# Adafruit_Proto_Tripler_PiCowbell.net
KiCad netlist of a schematic drawn in EAGLE
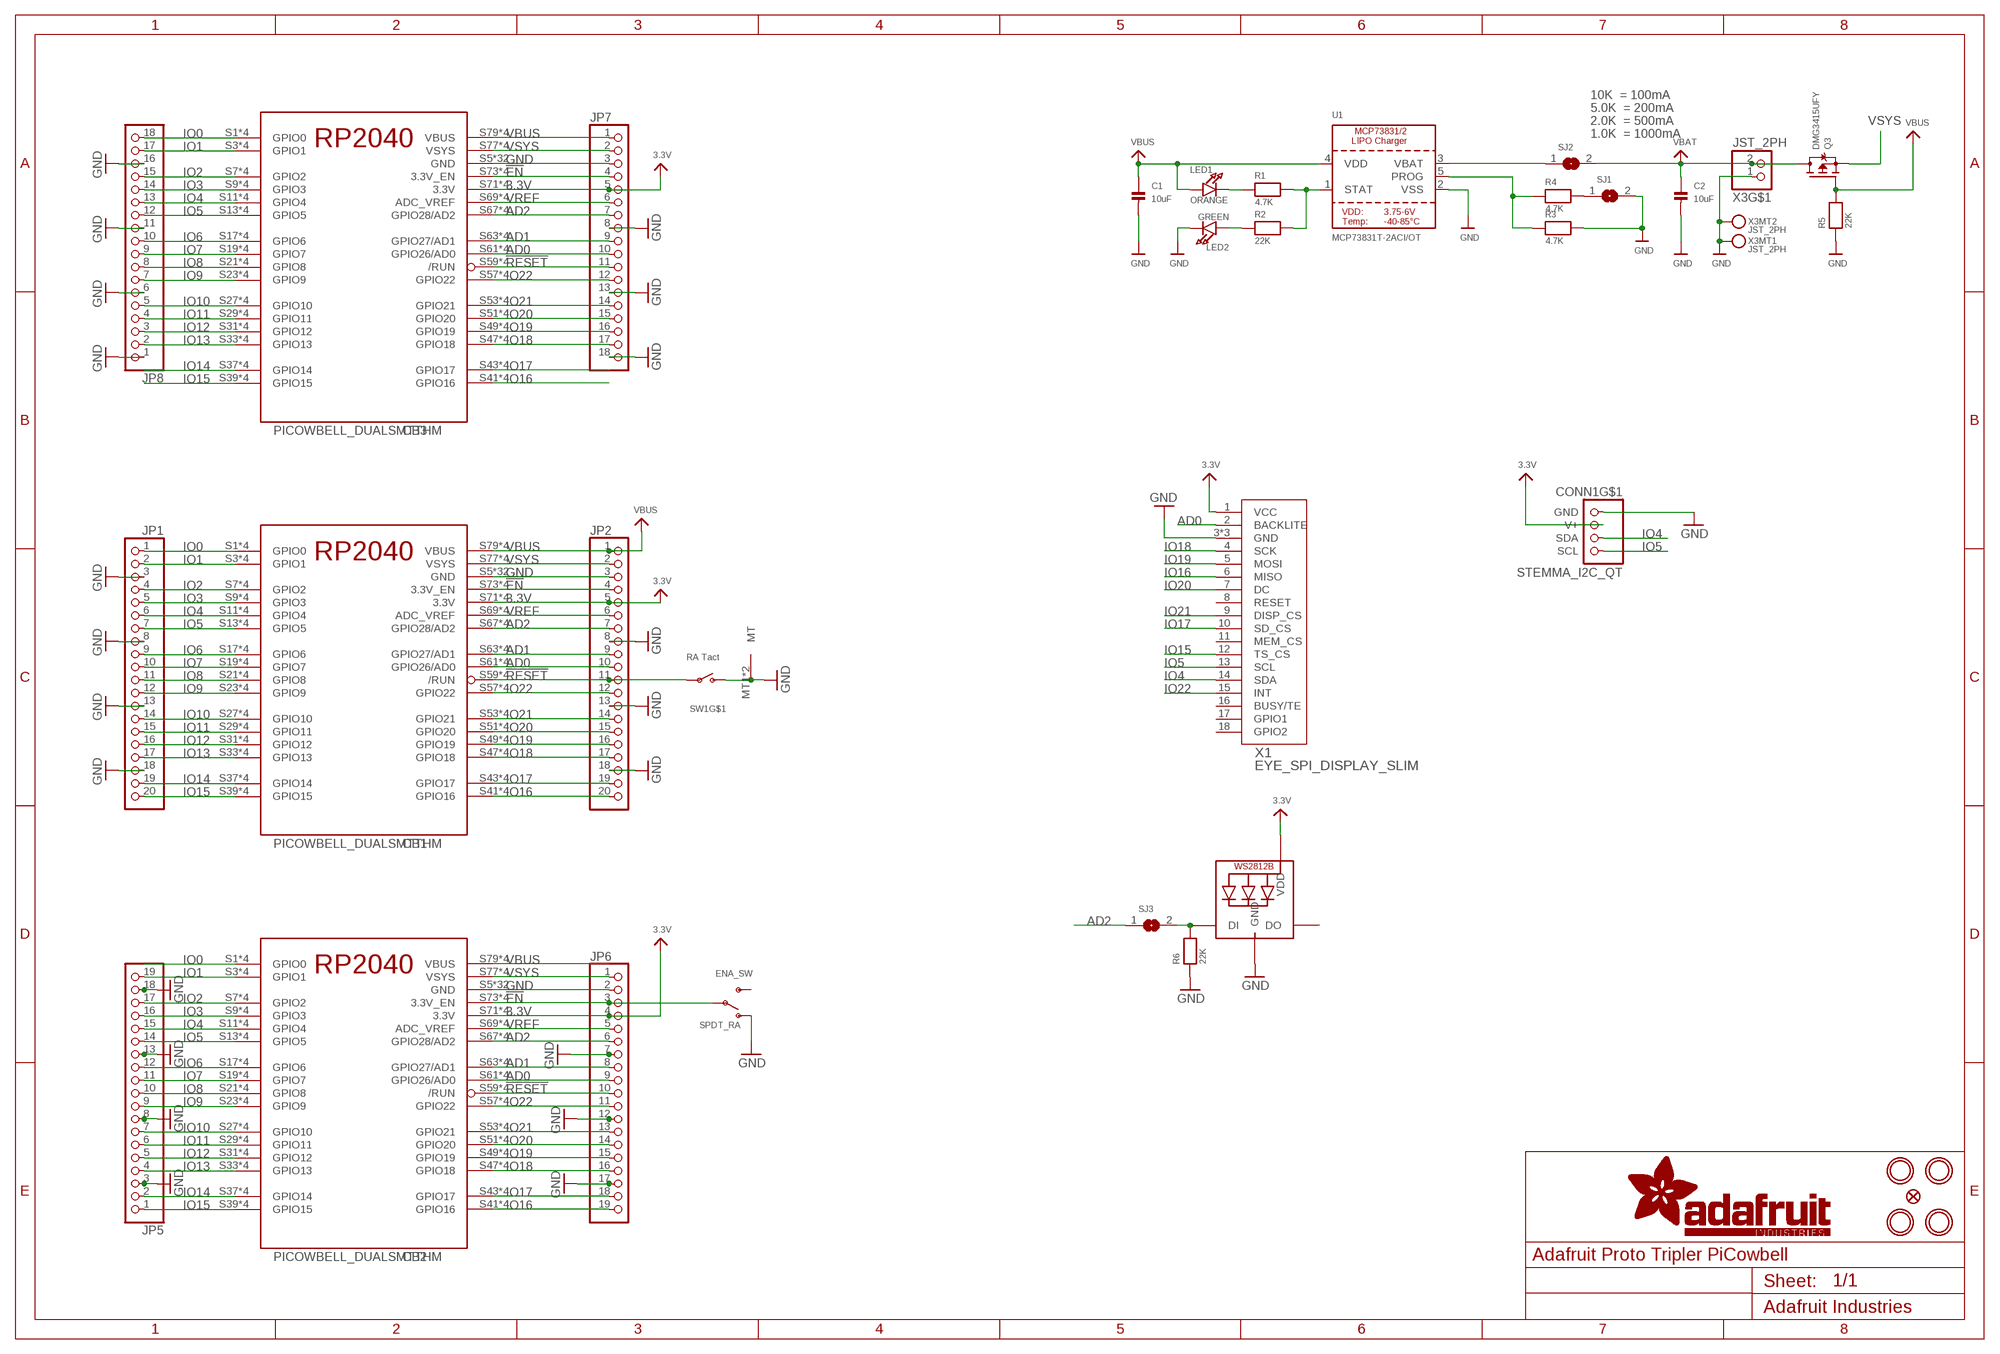
[diagram p0: schematic, sheet 1]

(export (version "E")
  (design (tool "Eeschema 10.0.6"))
  (components
    (comp (ref "C1")
      (value "10uF")
      (footprint "eagle-import:0805-NO")
      (libsource (lib "eagle-import") (part "CAP_CERAMIC0805-NOOUTLINE"))
    )
    (comp (ref "C2")
      (value "10uF")
      (footprint "eagle-import:0805-NO")
      (libsource (lib "eagle-import") (part "CAP_CERAMIC0805-NOOUTLINE"))
    )
    (comp (ref "CB1")
      (value "PICOWBELL_DUALSMTTHM")
      (footprint "eagle-import:PICOWBELL_DUALSMTTHM")
      (libsource (lib "eagle-import") (part "PICOWBELL_DUALSMTTHM"))
    )
    (comp (ref "CB2")
      (value "PICOWBELL_DUALSMTTHM")
      (footprint "eagle-import:PICOWBELL_DUALSMTTHM")
      (libsource (lib "eagle-import") (part "PICOWBELL_DUALSMTTHM"))
    )
    (comp (ref "CB3")
      (value "PICOWBELL_DUALSMTTHM")
      (footprint "eagle-import:PICOWBELL_DUALSMTTHM")
      (libsource (lib "eagle-import") (part "PICOWBELL_DUALSMTTHM"))
    )
    (comp (ref "CONN1")
      (value "STEMMA_I2C_QT")
      (footprint "eagle-import:JST_SH4")
      (libsource (lib "eagle-import") (part "STEMMA_I2C_QT"))
    )
    (comp (ref "ENA_SW")
      (value "SPDT_RA")
      (footprint "eagle-import:SPDT_SMT_SSSS811101")
      (libsource (lib "eagle-import") (part "SWITCH_SPDT"))
    )
    (comp (ref "FID2")
      (value "FIDUCIAL_1MM")
      (footprint "eagle-import:FIDUCIAL_1MM")
      (libsource (lib "eagle-import") (part "FIDUCIAL_1MM"))
    )
    (comp (ref "JP1")
      (value "HEADER-1X20_70MIL")
      (footprint "eagle-import:1X20_ROUND_70MIL")
      (libsource (lib "eagle-import") (part "HEADER-1X20_70MIL"))
    )
    (comp (ref "JP2")
      (value "HEADER-1X20_70MIL")
      (footprint "eagle-import:1X20_ROUND_70MIL")
      (libsource (lib "eagle-import") (part "HEADER-1X20_70MIL"))
    )
    (comp (ref "JP5")
      (value "HEADER-1X19")
      (footprint "eagle-import:1X19_ROUND")
      (libsource (lib "eagle-import") (part "HEADER-1X19"))
    )
    (comp (ref "JP6")
      (value "HEADER-1X19")
      (footprint "eagle-import:1X19_ROUND")
      (libsource (lib "eagle-import") (part "HEADER-1X19"))
    )
    (comp (ref "JP7")
      (value "HEADER-1X18")
      (footprint "eagle-import:1X18_ROUND70")
      (libsource (lib "eagle-import") (part "HEADER-1X18"))
    )
    (comp (ref "JP8")
      (value "HEADER-1X18")
      (footprint "eagle-import:1X18_ROUND70")
      (libsource (lib "eagle-import") (part "HEADER-1X18"))
    )
    (comp (ref "LED1")
      (value "ORANGE")
      (footprint "eagle-import:CHIPLED_0603_NOOUTLINE")
      (libsource (lib "eagle-import") (part "LED0603_NOOUTLINE"))
    )
    (comp (ref "LED2")
      (value "GREEN")
      (footprint "eagle-import:CHIPLED_0603_NOOUTLINE")
      (libsource (lib "eagle-import") (part "LED0603_NOOUTLINE"))
    )
    (comp (ref "LED3")
      (value "WS2812B_3535FULL")
      (footprint "eagle-import:LED3535_FULLPADS")
      (libsource (lib "eagle-import") (part "WS2812B_3535FULL"))
    )
    (comp (ref "Q3")
      (value "DMG3415UFY")
      (footprint "eagle-import:DFN2015-3")
      (libsource (lib "eagle-import") (part "MOSFET-P_DFN2015"))
    )
    (comp (ref "R1")
      (value "4.7K")
      (footprint "eagle-import:_0402NO")
      (libsource (lib "eagle-import") (part "RESISTOR_0402NO"))
    )
    (comp (ref "R2")
      (value "22K")
      (footprint "eagle-import:_0402NO")
      (libsource (lib "eagle-import") (part "RESISTOR_0402NO"))
    )
    (comp (ref "R3")
      (value "4.7K")
      (footprint "eagle-import:_0402NO")
      (libsource (lib "eagle-import") (part "RESISTOR_0402NO"))
    )
    (comp (ref "R4")
      (value "4.7K")
      (footprint "eagle-import:_0402NO")
      (libsource (lib "eagle-import") (part "RESISTOR_0402NO"))
    )
    (comp (ref "R5")
      (value "22K")
      (footprint "eagle-import:_0402NO")
      (libsource (lib "eagle-import") (part "RESISTOR_0402NO"))
    )
    (comp (ref "R6")
      (value "22K")
      (footprint "eagle-import:_0402NO")
      (libsource (lib "eagle-import") (part "RESISTOR_0402NO"))
    )
    (comp (ref "SJ1")
      (value "SOLDERJUMPERCLOSED")
      (footprint "eagle-import:SOLDERJUMPER_CLOSEDWIRE")
      (libsource (lib "eagle-import") (part "SOLDERJUMPERCLOSED"))
    )
    (comp (ref "SJ2")
      (value "SOLDERJUMPERCLOSED")
      (footprint "eagle-import:SOLDERJUMPER_CLOSEDWIRE")
      (libsource (lib "eagle-import") (part "SOLDERJUMPERCLOSED"))
    )
    (comp (ref "SJ3")
      (value "SOLDERJUMPERCLOSED")
      (footprint "eagle-import:SOLDERJUMPER_CLOSEDWIRE")
      (libsource (lib "eagle-import") (part "SOLDERJUMPERCLOSED"))
    )
    (comp (ref "SW1")
      (value "RA Tact")
      (footprint "eagle-import:SPST_TACTILE_RA")
      (libsource (lib "eagle-import") (part "SWITCH_SPST_MNT_TACT_RA"))
    )
    (comp (ref "U$5")
      (value "MOUNTINGHOLE2.5")
      (footprint "eagle-import:MOUNTINGHOLE_2.5_PLATED")
      (libsource (lib "eagle-import") (part "MOUNTINGHOLE2.5"))
    )
    (comp (ref "U$7")
      (value "MOUNTINGHOLE2.5")
      (footprint "eagle-import:MOUNTINGHOLE_2.5_PLATED")
      (libsource (lib "eagle-import") (part "MOUNTINGHOLE2.5"))
    )
    (comp (ref "U$15")
      (value "MOUNTINGHOLE2.5")
      (footprint "eagle-import:MOUNTINGHOLE_2.5_PLATED")
      (libsource (lib "eagle-import") (part "MOUNTINGHOLE2.5"))
    )
    (comp (ref "U$16")
      (value "MOUNTINGHOLE2.5")
      (footprint "eagle-import:MOUNTINGHOLE_2.5_PLATED")
      (libsource (lib "eagle-import") (part "MOUNTINGHOLE2.5"))
    )
    (comp (ref "U1")
      (value "MCP73831T-2ACI/OT")
      (footprint "eagle-import:SOT23-5")
      (fields (field (name "JLC_ROTATION") "0"))
      (libsource (lib "eagle-import") (part "MCP73831/2"))
    )
    (comp (ref "X1")
      (value "EYE_SPI_DISPLAY_SLIM")
      (footprint "eagle-import:EYE_SPI_DISPLAY_SLIM")
      (libsource (lib "eagle-import") (part "EYE_SPI_DISPLAY_SLIM"))
    )
    (comp (ref "X3")
      (value "JST_2PH")
      (footprint "eagle-import:JSTPH2_BATT")
      (libsource (lib "eagle-import") (part "CON_JST_PH_2PIN_MT_BATT"))
    )
  )
  (nets
    (net (code "1") (name "/AD0") (class "Default")
      (node (ref "CB1") (pin "S61") (pinfunction "GPIO26/AD0_S61") (pintype "bidirectional"))
      (node (ref "CB1") (pin "S62") (pinfunction "GPIO26/AD0_S62") (pintype "bidirectional"))
      (node (ref "CB1") (pin "T61") (pinfunction "GPIO26/AD0_T61") (pintype "bidirectional"))
      (node (ref "CB1") (pin "T62") (pinfunction "GPIO26/AD0_T62") (pintype "bidirectional"))
      (node (ref "CB2") (pin "S61") (pinfunction "GPIO26/AD0_S61") (pintype "bidirectional"))
      (node (ref "CB2") (pin "S62") (pinfunction "GPIO26/AD0_S62") (pintype "bidirectional"))
      (node (ref "CB2") (pin "T61") (pinfunction "GPIO26/AD0_T61") (pintype "bidirectional"))
      (node (ref "CB2") (pin "T62") (pinfunction "GPIO26/AD0_T62") (pintype "bidirectional"))
      (node (ref "CB3") (pin "S61") (pinfunction "GPIO26/AD0_S61") (pintype "bidirectional"))
      (node (ref "CB3") (pin "S62") (pinfunction "GPIO26/AD0_S62") (pintype "bidirectional"))
      (node (ref "CB3") (pin "T61") (pinfunction "GPIO26/AD0_T61") (pintype "bidirectional"))
      (node (ref "CB3") (pin "T62") (pinfunction "GPIO26/AD0_T62") (pintype "bidirectional"))
      (node (ref "JP2") (pin "10") (pinfunction "10_10") (pintype "passive"))
      (node (ref "JP6") (pin "9") (pinfunction "9_9") (pintype "passive"))
      (node (ref "JP7") (pin "10") (pinfunction "10_10") (pintype "passive"))
      (node (ref "X1") (pin "2") (pinfunction "BACKLITE_2") (pintype "input"))
    )
    (net (code "2") (name "/AD1") (class "Default")
      (node (ref "CB1") (pin "S63") (pinfunction "GPIO27/AD1_S63") (pintype "bidirectional"))
      (node (ref "CB1") (pin "S64") (pinfunction "GPIO27/AD1_S64") (pintype "bidirectional"))
      (node (ref "CB1") (pin "T63") (pinfunction "GPIO27/AD1_T63") (pintype "bidirectional"))
      (node (ref "CB1") (pin "T64") (pinfunction "GPIO27/AD1_T64") (pintype "bidirectional"))
      (node (ref "CB2") (pin "S63") (pinfunction "GPIO27/AD1_S63") (pintype "bidirectional"))
      (node (ref "CB2") (pin "S64") (pinfunction "GPIO27/AD1_S64") (pintype "bidirectional"))
      (node (ref "CB2") (pin "T63") (pinfunction "GPIO27/AD1_T63") (pintype "bidirectional"))
      (node (ref "CB2") (pin "T64") (pinfunction "GPIO27/AD1_T64") (pintype "bidirectional"))
      (node (ref "CB3") (pin "S63") (pinfunction "GPIO27/AD1_S63") (pintype "bidirectional"))
      (node (ref "CB3") (pin "S64") (pinfunction "GPIO27/AD1_S64") (pintype "bidirectional"))
      (node (ref "CB3") (pin "T63") (pinfunction "GPIO27/AD1_T63") (pintype "bidirectional"))
      (node (ref "CB3") (pin "T64") (pinfunction "GPIO27/AD1_T64") (pintype "bidirectional"))
      (node (ref "JP2") (pin "9") (pinfunction "9_9") (pintype "passive"))
      (node (ref "JP6") (pin "8") (pinfunction "8_8") (pintype "passive"))
      (node (ref "JP7") (pin "9") (pinfunction "9_9") (pintype "passive"))
    )
    (net (code "3") (name "/AD2") (class "Default")
      (node (ref "CB1") (pin "S67") (pinfunction "GPIO28/AD2_S67") (pintype "bidirectional"))
      (node (ref "CB1") (pin "S68") (pinfunction "GPIO28/AD2_S68") (pintype "bidirectional"))
      (node (ref "CB1") (pin "T67") (pinfunction "GPIO28/AD2_T67") (pintype "bidirectional"))
      (node (ref "CB1") (pin "T68") (pinfunction "GPIO28/AD2_T68") (pintype "bidirectional"))
      (node (ref "CB2") (pin "S67") (pinfunction "GPIO28/AD2_S67") (pintype "bidirectional"))
      (node (ref "CB2") (pin "S68") (pinfunction "GPIO28/AD2_S68") (pintype "bidirectional"))
      (node (ref "CB2") (pin "T67") (pinfunction "GPIO28/AD2_T67") (pintype "bidirectional"))
      (node (ref "CB2") (pin "T68") (pinfunction "GPIO28/AD2_T68") (pintype "bidirectional"))
      (node (ref "CB3") (pin "S67") (pinfunction "GPIO28/AD2_S67") (pintype "bidirectional"))
      (node (ref "CB3") (pin "S68") (pinfunction "GPIO28/AD2_S68") (pintype "bidirectional"))
      (node (ref "CB3") (pin "T67") (pinfunction "GPIO28/AD2_T67") (pintype "bidirectional"))
      (node (ref "CB3") (pin "T68") (pinfunction "GPIO28/AD2_T68") (pintype "bidirectional"))
      (node (ref "JP2") (pin "7") (pinfunction "7_7") (pintype "passive"))
      (node (ref "JP6") (pin "6") (pinfunction "6_6") (pintype "passive"))
      (node (ref "JP7") (pin "7") (pinfunction "7_7") (pintype "passive"))
      (node (ref "SJ3") (pin "1") (pinfunction "1_1") (pintype "passive"))
    )
    (net (code "4") (name "/IO0") (class "Default")
      (node (ref "CB1") (pin "S1") (pinfunction "GPIO0_S1") (pintype "bidirectional"))
      (node (ref "CB1") (pin "S2") (pinfunction "GPIO0_S2") (pintype "bidirectional"))
      (node (ref "CB1") (pin "T1") (pinfunction "GPIO0_T1") (pintype "bidirectional"))
      (node (ref "CB1") (pin "T2") (pinfunction "GPIO0_T2") (pintype "bidirectional"))
      (node (ref "CB2") (pin "S1") (pinfunction "GPIO0_S1") (pintype "bidirectional"))
      (node (ref "CB2") (pin "S2") (pinfunction "GPIO0_S2") (pintype "bidirectional"))
      (node (ref "CB2") (pin "T1") (pinfunction "GPIO0_T1") (pintype "bidirectional"))
      (node (ref "CB2") (pin "T2") (pinfunction "GPIO0_T2") (pintype "bidirectional"))
      (node (ref "CB3") (pin "S1") (pinfunction "GPIO0_S1") (pintype "bidirectional"))
      (node (ref "CB3") (pin "S2") (pinfunction "GPIO0_S2") (pintype "bidirectional"))
      (node (ref "CB3") (pin "T1") (pinfunction "GPIO0_T1") (pintype "bidirectional"))
      (node (ref "CB3") (pin "T2") (pinfunction "GPIO0_T2") (pintype "bidirectional"))
      (node (ref "JP1") (pin "1") (pinfunction "1_1") (pintype "passive"))
      (node (ref "JP8") (pin "18") (pinfunction "18_18") (pintype "passive"))
    )
    (net (code "5") (name "/IO1") (class "Default")
      (node (ref "CB1") (pin "S3") (pinfunction "GPIO1_S3") (pintype "bidirectional"))
      (node (ref "CB1") (pin "S4") (pinfunction "GPIO1_S4") (pintype "bidirectional"))
      (node (ref "CB1") (pin "T3") (pinfunction "GPIO1_T3") (pintype "bidirectional"))
      (node (ref "CB1") (pin "T4") (pinfunction "GPIO1_T4") (pintype "bidirectional"))
      (node (ref "CB2") (pin "S3") (pinfunction "GPIO1_S3") (pintype "bidirectional"))
      (node (ref "CB2") (pin "S4") (pinfunction "GPIO1_S4") (pintype "bidirectional"))
      (node (ref "CB2") (pin "T3") (pinfunction "GPIO1_T3") (pintype "bidirectional"))
      (node (ref "CB2") (pin "T4") (pinfunction "GPIO1_T4") (pintype "bidirectional"))
      (node (ref "CB3") (pin "S3") (pinfunction "GPIO1_S3") (pintype "bidirectional"))
      (node (ref "CB3") (pin "S4") (pinfunction "GPIO1_S4") (pintype "bidirectional"))
      (node (ref "CB3") (pin "T3") (pinfunction "GPIO1_T3") (pintype "bidirectional"))
      (node (ref "CB3") (pin "T4") (pinfunction "GPIO1_T4") (pintype "bidirectional"))
      (node (ref "JP1") (pin "2") (pinfunction "2_2") (pintype "passive"))
      (node (ref "JP5") (pin "19") (pinfunction "19_19") (pintype "passive"))
      (node (ref "JP8") (pin "17") (pinfunction "17_17") (pintype "passive"))
    )
    (net (code "6") (name "/IO2") (class "Default")
      (node (ref "CB1") (pin "S7") (pinfunction "GPIO2_S7") (pintype "bidirectional"))
      (node (ref "CB1") (pin "S8") (pinfunction "GPIO2_S8") (pintype "bidirectional"))
      (node (ref "CB1") (pin "T7") (pinfunction "GPIO2_T7") (pintype "bidirectional"))
      (node (ref "CB1") (pin "T8") (pinfunction "GPIO2_T8") (pintype "bidirectional"))
      (node (ref "CB2") (pin "S7") (pinfunction "GPIO2_S7") (pintype "bidirectional"))
      (node (ref "CB2") (pin "S8") (pinfunction "GPIO2_S8") (pintype "bidirectional"))
      (node (ref "CB2") (pin "T7") (pinfunction "GPIO2_T7") (pintype "bidirectional"))
      (node (ref "CB2") (pin "T8") (pinfunction "GPIO2_T8") (pintype "bidirectional"))
      (node (ref "CB3") (pin "S7") (pinfunction "GPIO2_S7") (pintype "bidirectional"))
      (node (ref "CB3") (pin "S8") (pinfunction "GPIO2_S8") (pintype "bidirectional"))
      (node (ref "CB3") (pin "T7") (pinfunction "GPIO2_T7") (pintype "bidirectional"))
      (node (ref "CB3") (pin "T8") (pinfunction "GPIO2_T8") (pintype "bidirectional"))
      (node (ref "JP1") (pin "4") (pinfunction "4_4") (pintype "passive"))
      (node (ref "JP5") (pin "17") (pinfunction "17_17") (pintype "passive"))
      (node (ref "JP8") (pin "15") (pinfunction "15_15") (pintype "passive"))
    )
    (net (code "7") (name "/IO3") (class "Default")
      (node (ref "CB1") (pin "S10") (pinfunction "GPIO3_S10") (pintype "bidirectional"))
      (node (ref "CB1") (pin "S9") (pinfunction "GPIO3_S9") (pintype "bidirectional"))
      (node (ref "CB1") (pin "T10") (pinfunction "GPIO3_T10") (pintype "bidirectional"))
      (node (ref "CB1") (pin "T9") (pinfunction "GPIO3_T9") (pintype "bidirectional"))
      (node (ref "CB2") (pin "S10") (pinfunction "GPIO3_S10") (pintype "bidirectional"))
      (node (ref "CB2") (pin "S9") (pinfunction "GPIO3_S9") (pintype "bidirectional"))
      (node (ref "CB2") (pin "T10") (pinfunction "GPIO3_T10") (pintype "bidirectional"))
      (node (ref "CB2") (pin "T9") (pinfunction "GPIO3_T9") (pintype "bidirectional"))
      (node (ref "CB3") (pin "S10") (pinfunction "GPIO3_S10") (pintype "bidirectional"))
      (node (ref "CB3") (pin "S9") (pinfunction "GPIO3_S9") (pintype "bidirectional"))
      (node (ref "CB3") (pin "T10") (pinfunction "GPIO3_T10") (pintype "bidirectional"))
      (node (ref "CB3") (pin "T9") (pinfunction "GPIO3_T9") (pintype "bidirectional"))
      (node (ref "JP1") (pin "5") (pinfunction "5_5") (pintype "passive"))
      (node (ref "JP5") (pin "16") (pinfunction "16_16") (pintype "passive"))
      (node (ref "JP8") (pin "14") (pinfunction "14_14") (pintype "passive"))
    )
    (net (code "8") (name "/IO4") (class "Default")
      (node (ref "CB1") (pin "S11") (pinfunction "GPIO4_S11") (pintype "bidirectional"))
      (node (ref "CB1") (pin "S12") (pinfunction "GPIO4_S12") (pintype "bidirectional"))
      (node (ref "CB1") (pin "T11") (pinfunction "GPIO4_T11") (pintype "bidirectional"))
      (node (ref "CB1") (pin "T12") (pinfunction "GPIO4_T12") (pintype "bidirectional"))
      (node (ref "CB2") (pin "S11") (pinfunction "GPIO4_S11") (pintype "bidirectional"))
      (node (ref "CB2") (pin "S12") (pinfunction "GPIO4_S12") (pintype "bidirectional"))
      (node (ref "CB2") (pin "T11") (pinfunction "GPIO4_T11") (pintype "bidirectional"))
      (node (ref "CB2") (pin "T12") (pinfunction "GPIO4_T12") (pintype "bidirectional"))
      (node (ref "CB3") (pin "S11") (pinfunction "GPIO4_S11") (pintype "bidirectional"))
      (node (ref "CB3") (pin "S12") (pinfunction "GPIO4_S12") (pintype "bidirectional"))
      (node (ref "CB3") (pin "T11") (pinfunction "GPIO4_T11") (pintype "bidirectional"))
      (node (ref "CB3") (pin "T12") (pinfunction "GPIO4_T12") (pintype "bidirectional"))
      (node (ref "CONN1") (pin "3") (pinfunction "SDA_3") (pintype "passive"))
      (node (ref "JP1") (pin "6") (pinfunction "6_6") (pintype "passive"))
      (node (ref "JP5") (pin "15") (pinfunction "15_15") (pintype "passive"))
      (node (ref "JP8") (pin "13") (pinfunction "13_13") (pintype "passive"))
      (node (ref "X1") (pin "14") (pinfunction "SDA_14") (pintype "bidirectional"))
    )
    (net (code "9") (name "/IO5") (class "Default")
      (node (ref "CB1") (pin "S13") (pinfunction "GPIO5_S13") (pintype "bidirectional"))
      (node (ref "CB1") (pin "S14") (pinfunction "GPIO5_S14") (pintype "bidirectional"))
      (node (ref "CB1") (pin "T13") (pinfunction "GPIO5_T13") (pintype "bidirectional"))
      (node (ref "CB1") (pin "T14") (pinfunction "GPIO5_T14") (pintype "bidirectional"))
      (node (ref "CB2") (pin "S13") (pinfunction "GPIO5_S13") (pintype "bidirectional"))
      (node (ref "CB2") (pin "S14") (pinfunction "GPIO5_S14") (pintype "bidirectional"))
      (node (ref "CB2") (pin "T13") (pinfunction "GPIO5_T13") (pintype "bidirectional"))
      (node (ref "CB2") (pin "T14") (pinfunction "GPIO5_T14") (pintype "bidirectional"))
      (node (ref "CB3") (pin "S13") (pinfunction "GPIO5_S13") (pintype "bidirectional"))
      (node (ref "CB3") (pin "S14") (pinfunction "GPIO5_S14") (pintype "bidirectional"))
      (node (ref "CB3") (pin "T13") (pinfunction "GPIO5_T13") (pintype "bidirectional"))
      (node (ref "CB3") (pin "T14") (pinfunction "GPIO5_T14") (pintype "bidirectional"))
      (node (ref "CONN1") (pin "4") (pinfunction "SCL_4") (pintype "passive"))
      (node (ref "JP1") (pin "7") (pinfunction "7_7") (pintype "passive"))
      (node (ref "JP5") (pin "14") (pinfunction "14_14") (pintype "passive"))
      (node (ref "JP8") (pin "12") (pinfunction "12_12") (pintype "passive"))
      (node (ref "X1") (pin "13") (pinfunction "SCL_13") (pintype "input"))
    )
    (net (code "10") (name "/IO6") (class "Default")
      (node (ref "CB1") (pin "S17") (pinfunction "GPIO6_S17") (pintype "bidirectional"))
      (node (ref "CB1") (pin "S18") (pinfunction "GPIO6_S18") (pintype "bidirectional"))
      (node (ref "CB1") (pin "T17") (pinfunction "GPIO6_T17") (pintype "bidirectional"))
      (node (ref "CB1") (pin "T18") (pinfunction "GPIO6_T18") (pintype "bidirectional"))
      (node (ref "CB2") (pin "S17") (pinfunction "GPIO6_S17") (pintype "bidirectional"))
      (node (ref "CB2") (pin "S18") (pinfunction "GPIO6_S18") (pintype "bidirectional"))
      (node (ref "CB2") (pin "T17") (pinfunction "GPIO6_T17") (pintype "bidirectional"))
      (node (ref "CB2") (pin "T18") (pinfunction "GPIO6_T18") (pintype "bidirectional"))
      (node (ref "CB3") (pin "S17") (pinfunction "GPIO6_S17") (pintype "bidirectional"))
      (node (ref "CB3") (pin "S18") (pinfunction "GPIO6_S18") (pintype "bidirectional"))
      (node (ref "CB3") (pin "T17") (pinfunction "GPIO6_T17") (pintype "bidirectional"))
      (node (ref "CB3") (pin "T18") (pinfunction "GPIO6_T18") (pintype "bidirectional"))
      (node (ref "JP1") (pin "9") (pinfunction "9_9") (pintype "passive"))
      (node (ref "JP5") (pin "12") (pinfunction "12_12") (pintype "passive"))
      (node (ref "JP8") (pin "10") (pinfunction "10_10") (pintype "passive"))
    )
    (net (code "11") (name "/IO7") (class "Default")
      (node (ref "CB1") (pin "S19") (pinfunction "GPIO7_S19") (pintype "bidirectional"))
      (node (ref "CB1") (pin "S20") (pinfunction "GPIO7_S20") (pintype "bidirectional"))
      (node (ref "CB1") (pin "T19") (pinfunction "GPIO7_T19") (pintype "bidirectional"))
      (node (ref "CB1") (pin "T20") (pinfunction "GPIO7_T20") (pintype "bidirectional"))
      (node (ref "CB2") (pin "S19") (pinfunction "GPIO7_S19") (pintype "bidirectional"))
      (node (ref "CB2") (pin "S20") (pinfunction "GPIO7_S20") (pintype "bidirectional"))
      (node (ref "CB2") (pin "T19") (pinfunction "GPIO7_T19") (pintype "bidirectional"))
      (node (ref "CB2") (pin "T20") (pinfunction "GPIO7_T20") (pintype "bidirectional"))
      (node (ref "CB3") (pin "S19") (pinfunction "GPIO7_S19") (pintype "bidirectional"))
      (node (ref "CB3") (pin "S20") (pinfunction "GPIO7_S20") (pintype "bidirectional"))
      (node (ref "CB3") (pin "T19") (pinfunction "GPIO7_T19") (pintype "bidirectional"))
      (node (ref "CB3") (pin "T20") (pinfunction "GPIO7_T20") (pintype "bidirectional"))
      (node (ref "JP1") (pin "10") (pinfunction "10_10") (pintype "passive"))
      (node (ref "JP5") (pin "11") (pinfunction "11_11") (pintype "passive"))
      (node (ref "JP8") (pin "9") (pinfunction "9_9") (pintype "passive"))
    )
    (net (code "12") (name "/IO8") (class "Default")
      (node (ref "CB1") (pin "S21") (pinfunction "GPIO8_S21") (pintype "bidirectional"))
      (node (ref "CB1") (pin "S22") (pinfunction "GPIO8_S22") (pintype "bidirectional"))
      (node (ref "CB1") (pin "T21") (pinfunction "GPIO8_T21") (pintype "bidirectional"))
      (node (ref "CB1") (pin "T22") (pinfunction "GPIO8_T22") (pintype "bidirectional"))
      (node (ref "CB2") (pin "S21") (pinfunction "GPIO8_S21") (pintype "bidirectional"))
      (node (ref "CB2") (pin "S22") (pinfunction "GPIO8_S22") (pintype "bidirectional"))
      (node (ref "CB2") (pin "T21") (pinfunction "GPIO8_T21") (pintype "bidirectional"))
      (node (ref "CB2") (pin "T22") (pinfunction "GPIO8_T22") (pintype "bidirectional"))
      (node (ref "CB3") (pin "S21") (pinfunction "GPIO8_S21") (pintype "bidirectional"))
      (node (ref "CB3") (pin "S22") (pinfunction "GPIO8_S22") (pintype "bidirectional"))
      (node (ref "CB3") (pin "T21") (pinfunction "GPIO8_T21") (pintype "bidirectional"))
      (node (ref "CB3") (pin "T22") (pinfunction "GPIO8_T22") (pintype "bidirectional"))
      (node (ref "JP1") (pin "11") (pinfunction "11_11") (pintype "passive"))
      (node (ref "JP5") (pin "10") (pinfunction "10_10") (pintype "passive"))
      (node (ref "JP8") (pin "8") (pinfunction "8_8") (pintype "passive"))
    )
    (net (code "13") (name "/IO9") (class "Default")
      (node (ref "CB1") (pin "S23") (pinfunction "GPIO9_S23") (pintype "bidirectional"))
      (node (ref "CB1") (pin "S24") (pinfunction "GPIO9_S24") (pintype "bidirectional"))
      (node (ref "CB1") (pin "T23") (pinfunction "GPIO9_T23") (pintype "bidirectional"))
      (node (ref "CB1") (pin "T24") (pinfunction "GPIO9_T24") (pintype "bidirectional"))
      (node (ref "CB2") (pin "S23") (pinfunction "GPIO9_S23") (pintype "bidirectional"))
      (node (ref "CB2") (pin "S24") (pinfunction "GPIO9_S24") (pintype "bidirectional"))
      (node (ref "CB2") (pin "T23") (pinfunction "GPIO9_T23") (pintype "bidirectional"))
      (node (ref "CB2") (pin "T24") (pinfunction "GPIO9_T24") (pintype "bidirectional"))
      (node (ref "CB3") (pin "S23") (pinfunction "GPIO9_S23") (pintype "bidirectional"))
      (node (ref "CB3") (pin "S24") (pinfunction "GPIO9_S24") (pintype "bidirectional"))
      (node (ref "CB3") (pin "T23") (pinfunction "GPIO9_T23") (pintype "bidirectional"))
      (node (ref "CB3") (pin "T24") (pinfunction "GPIO9_T24") (pintype "bidirectional"))
      (node (ref "JP1") (pin "12") (pinfunction "12_12") (pintype "passive"))
      (node (ref "JP5") (pin "9") (pinfunction "9_9") (pintype "passive"))
      (node (ref "JP8") (pin "7") (pinfunction "7_7") (pintype "passive"))
    )
    (net (code "14") (name "/IO10") (class "Default")
      (node (ref "CB1") (pin "S27") (pinfunction "GPIO10_S27") (pintype "bidirectional"))
      (node (ref "CB1") (pin "S28") (pinfunction "GPIO10_S28") (pintype "bidirectional"))
      (node (ref "CB1") (pin "T27") (pinfunction "GPIO10_T27") (pintype "bidirectional"))
      (node (ref "CB1") (pin "T28") (pinfunction "GPIO10_T28") (pintype "bidirectional"))
      (node (ref "CB2") (pin "S27") (pinfunction "GPIO10_S27") (pintype "bidirectional"))
      (node (ref "CB2") (pin "S28") (pinfunction "GPIO10_S28") (pintype "bidirectional"))
      (node (ref "CB2") (pin "T27") (pinfunction "GPIO10_T27") (pintype "bidirectional"))
      (node (ref "CB2") (pin "T28") (pinfunction "GPIO10_T28") (pintype "bidirectional"))
      (node (ref "CB3") (pin "S27") (pinfunction "GPIO10_S27") (pintype "bidirectional"))
      (node (ref "CB3") (pin "S28") (pinfunction "GPIO10_S28") (pintype "bidirectional"))
      (node (ref "CB3") (pin "T27") (pinfunction "GPIO10_T27") (pintype "bidirectional"))
      (node (ref "CB3") (pin "T28") (pinfunction "GPIO10_T28") (pintype "bidirectional"))
      (node (ref "JP1") (pin "14") (pinfunction "14_14") (pintype "passive"))
      (node (ref "JP5") (pin "7") (pinfunction "7_7") (pintype "passive"))
      (node (ref "JP8") (pin "5") (pinfunction "5_5") (pintype "passive"))
    )
    (net (code "15") (name "/IO11") (class "Default")
      (node (ref "CB1") (pin "S29") (pinfunction "GPIO11_S29") (pintype "bidirectional"))
      (node (ref "CB1") (pin "S30") (pinfunction "GPIO11_S30") (pintype "bidirectional"))
      (node (ref "CB1") (pin "T29") (pinfunction "GPIO11_T29") (pintype "bidirectional"))
      (node (ref "CB1") (pin "T30") (pinfunction "GPIO11_T30") (pintype "bidirectional"))
      (node (ref "CB2") (pin "S29") (pinfunction "GPIO11_S29") (pintype "bidirectional"))
      (node (ref "CB2") (pin "S30") (pinfunction "GPIO11_S30") (pintype "bidirectional"))
      (node (ref "CB2") (pin "T29") (pinfunction "GPIO11_T29") (pintype "bidirectional"))
      (node (ref "CB2") (pin "T30") (pinfunction "GPIO11_T30") (pintype "bidirectional"))
      (node (ref "CB3") (pin "S29") (pinfunction "GPIO11_S29") (pintype "bidirectional"))
      (node (ref "CB3") (pin "S30") (pinfunction "GPIO11_S30") (pintype "bidirectional"))
      (node (ref "CB3") (pin "T29") (pinfunction "GPIO11_T29") (pintype "bidirectional"))
      (node (ref "CB3") (pin "T30") (pinfunction "GPIO11_T30") (pintype "bidirectional"))
      (node (ref "JP1") (pin "15") (pinfunction "15_15") (pintype "passive"))
      (node (ref "JP5") (pin "6") (pinfunction "6_6") (pintype "passive"))
      (node (ref "JP8") (pin "4") (pinfunction "4_4") (pintype "passive"))
    )
    (net (code "16") (name "/IO12") (class "Default")
      (node (ref "CB1") (pin "S31") (pinfunction "GPIO12_S31") (pintype "bidirectional"))
      (node (ref "CB1") (pin "S32") (pinfunction "GPIO12_S32") (pintype "bidirectional"))
      (node (ref "CB1") (pin "T31") (pinfunction "GPIO12_T31") (pintype "bidirectional"))
      (node (ref "CB1") (pin "T32") (pinfunction "GPIO12_T32") (pintype "bidirectional"))
      (node (ref "CB2") (pin "S31") (pinfunction "GPIO12_S31") (pintype "bidirectional"))
      (node (ref "CB2") (pin "S32") (pinfunction "GPIO12_S32") (pintype "bidirectional"))
      (node (ref "CB2") (pin "T31") (pinfunction "GPIO12_T31") (pintype "bidirectional"))
      (node (ref "CB2") (pin "T32") (pinfunction "GPIO12_T32") (pintype "bidirectional"))
      (node (ref "CB3") (pin "S31") (pinfunction "GPIO12_S31") (pintype "bidirectional"))
      (node (ref "CB3") (pin "S32") (pinfunction "GPIO12_S32") (pintype "bidirectional"))
      (node (ref "CB3") (pin "T31") (pinfunction "GPIO12_T31") (pintype "bidirectional"))
      (node (ref "CB3") (pin "T32") (pinfunction "GPIO12_T32") (pintype "bidirectional"))
      (node (ref "JP1") (pin "16") (pinfunction "16_16") (pintype "passive"))
      (node (ref "JP5") (pin "5") (pinfunction "5_5") (pintype "passive"))
      (node (ref "JP8") (pin "3") (pinfunction "3_3") (pintype "passive"))
    )
    (net (code "17") (name "/IO13") (class "Default")
      (node (ref "CB1") (pin "S33") (pinfunction "GPIO13_S33") (pintype "bidirectional"))
      (node (ref "CB1") (pin "S34") (pinfunction "GPIO13_S34") (pintype "bidirectional"))
      (node (ref "CB1") (pin "T33") (pinfunction "GPIO13_T33") (pintype "bidirectional"))
      (node (ref "CB1") (pin "T34") (pinfunction "GPIO13_T34") (pintype "bidirectional"))
      (node (ref "CB2") (pin "S33") (pinfunction "GPIO13_S33") (pintype "bidirectional"))
      (node (ref "CB2") (pin "S34") (pinfunction "GPIO13_S34") (pintype "bidirectional"))
      (node (ref "CB2") (pin "T33") (pinfunction "GPIO13_T33") (pintype "bidirectional"))
      (node (ref "CB2") (pin "T34") (pinfunction "GPIO13_T34") (pintype "bidirectional"))
      (node (ref "CB3") (pin "S33") (pinfunction "GPIO13_S33") (pintype "bidirectional"))
      (node (ref "CB3") (pin "S34") (pinfunction "GPIO13_S34") (pintype "bidirectional"))
      (node (ref "CB3") (pin "T33") (pinfunction "GPIO13_T33") (pintype "bidirectional"))
      (node (ref "CB3") (pin "T34") (pinfunction "GPIO13_T34") (pintype "bidirectional"))
      (node (ref "JP1") (pin "17") (pinfunction "17_17") (pintype "passive"))
      (node (ref "JP5") (pin "4") (pinfunction "4_4") (pintype "passive"))
      (node (ref "JP8") (pin "2") (pinfunction "2_2") (pintype "passive"))
    )
    (net (code "18") (name "/IO14") (class "Default")
      (node (ref "CB1") (pin "S37") (pinfunction "GPIO14_S37") (pintype "bidirectional"))
      (node (ref "CB1") (pin "S38") (pinfunction "GPIO14_S38") (pintype "bidirectional"))
      (node (ref "CB1") (pin "T37") (pinfunction "GPIO14_T37") (pintype "bidirectional"))
      (node (ref "CB1") (pin "T38") (pinfunction "GPIO14_T38") (pintype "bidirectional"))
      (node (ref "CB2") (pin "S37") (pinfunction "GPIO14_S37") (pintype "bidirectional"))
      (node (ref "CB2") (pin "S38") (pinfunction "GPIO14_S38") (pintype "bidirectional"))
      (node (ref "CB2") (pin "T37") (pinfunction "GPIO14_T37") (pintype "bidirectional"))
      (node (ref "CB2") (pin "T38") (pinfunction "GPIO14_T38") (pintype "bidirectional"))
      (node (ref "CB3") (pin "S37") (pinfunction "GPIO14_S37") (pintype "bidirectional"))
      (node (ref "CB3") (pin "S38") (pinfunction "GPIO14_S38") (pintype "bidirectional"))
      (node (ref "CB3") (pin "T37") (pinfunction "GPIO14_T37") (pintype "bidirectional"))
      (node (ref "CB3") (pin "T38") (pinfunction "GPIO14_T38") (pintype "bidirectional"))
      (node (ref "JP1") (pin "19") (pinfunction "19_19") (pintype "passive"))
      (node (ref "JP5") (pin "2") (pinfunction "2_2") (pintype "passive"))
    )
    (net (code "19") (name "/IO15") (class "Default")
      (node (ref "CB1") (pin "S39") (pinfunction "GPIO15_S39") (pintype "bidirectional"))
      (node (ref "CB1") (pin "S40") (pinfunction "GPIO15_S40") (pintype "bidirectional"))
      (node (ref "CB1") (pin "T39") (pinfunction "GPIO15_T39") (pintype "bidirectional"))
      (node (ref "CB1") (pin "T40") (pinfunction "GPIO15_T40") (pintype "bidirectional"))
      (node (ref "CB2") (pin "S39") (pinfunction "GPIO15_S39") (pintype "bidirectional"))
      (node (ref "CB2") (pin "S40") (pinfunction "GPIO15_S40") (pintype "bidirectional"))
      (node (ref "CB2") (pin "T39") (pinfunction "GPIO15_T39") (pintype "bidirectional"))
      (node (ref "CB2") (pin "T40") (pinfunction "GPIO15_T40") (pintype "bidirectional"))
      (node (ref "CB3") (pin "S39") (pinfunction "GPIO15_S39") (pintype "bidirectional"))
      (node (ref "CB3") (pin "S40") (pinfunction "GPIO15_S40") (pintype "bidirectional"))
      (node (ref "CB3") (pin "T39") (pinfunction "GPIO15_T39") (pintype "bidirectional"))
      (node (ref "CB3") (pin "T40") (pinfunction "GPIO15_T40") (pintype "bidirectional"))
      (node (ref "JP1") (pin "20") (pinfunction "20_20") (pintype "passive"))
      (node (ref "JP5") (pin "1") (pinfunction "1_1") (pintype "passive"))
      (node (ref "X1") (pin "12") (pinfunction "TS_CS_12") (pintype "input"))
    )
    (net (code "20") (name "/IO16") (class "Default")
      (node (ref "CB1") (pin "S41") (pinfunction "GPIO16_S41") (pintype "bidirectional"))
      (node (ref "CB1") (pin "S42") (pinfunction "GPIO16_S42") (pintype "bidirectional"))
      (node (ref "CB1") (pin "T41") (pinfunction "GPIO16_T41") (pintype "bidirectional"))
      (node (ref "CB1") (pin "T42") (pinfunction "GPIO16_T42") (pintype "bidirectional"))
      (node (ref "CB2") (pin "S41") (pinfunction "GPIO16_S41") (pintype "bidirectional"))
      (node (ref "CB2") (pin "S42") (pinfunction "GPIO16_S42") (pintype "bidirectional"))
      (node (ref "CB2") (pin "T41") (pinfunction "GPIO16_T41") (pintype "bidirectional"))
      (node (ref "CB2") (pin "T42") (pinfunction "GPIO16_T42") (pintype "bidirectional"))
      (node (ref "CB3") (pin "S41") (pinfunction "GPIO16_S41") (pintype "bidirectional"))
      (node (ref "CB3") (pin "S42") (pinfunction "GPIO16_S42") (pintype "bidirectional"))
      (node (ref "CB3") (pin "T41") (pinfunction "GPIO16_T41") (pintype "bidirectional"))
      (node (ref "CB3") (pin "T42") (pinfunction "GPIO16_T42") (pintype "bidirectional"))
      (node (ref "JP2") (pin "20") (pinfunction "20_20") (pintype "passive"))
      (node (ref "JP6") (pin "19") (pinfunction "19_19") (pintype "passive"))
      (node (ref "X1") (pin "6") (pinfunction "MISO_6") (pintype "output"))
    )
    (net (code "21") (name "/IO17") (class "Default")
      (node (ref "CB1") (pin "S43") (pinfunction "GPIO17_S43") (pintype "bidirectional"))
      (node (ref "CB1") (pin "S44") (pinfunction "GPIO17_S44") (pintype "bidirectional"))
      (node (ref "CB1") (pin "T43") (pinfunction "GPIO17_T43") (pintype "bidirectional"))
      (node (ref "CB1") (pin "T44") (pinfunction "GPIO17_T44") (pintype "bidirectional"))
      (node (ref "CB2") (pin "S43") (pinfunction "GPIO17_S43") (pintype "bidirectional"))
      (node (ref "CB2") (pin "S44") (pinfunction "GPIO17_S44") (pintype "bidirectional"))
      (node (ref "CB2") (pin "T43") (pinfunction "GPIO17_T43") (pintype "bidirectional"))
      (node (ref "CB2") (pin "T44") (pinfunction "GPIO17_T44") (pintype "bidirectional"))
      (node (ref "CB3") (pin "S43") (pinfunction "GPIO17_S43") (pintype "bidirectional"))
      (node (ref "CB3") (pin "S44") (pinfunction "GPIO17_S44") (pintype "bidirectional"))
      (node (ref "CB3") (pin "T43") (pinfunction "GPIO17_T43") (pintype "bidirectional"))
      (node (ref "CB3") (pin "T44") (pinfunction "GPIO17_T44") (pintype "bidirectional"))
      (node (ref "JP2") (pin "19") (pinfunction "19_19") (pintype "passive"))
      (node (ref "JP6") (pin "18") (pinfunction "18_18") (pintype "passive"))
      (node (ref "X1") (pin "10") (pinfunction "SD_CS_10") (pintype "input"))
    )
    (net (code "22") (name "/IO18") (class "Default")
      (node (ref "CB1") (pin "S47") (pinfunction "GPIO18_S47") (pintype "bidirectional"))
      (node (ref "CB1") (pin "S48") (pinfunction "GPIO18_S48") (pintype "bidirectional"))
      (node (ref "CB1") (pin "T47") (pinfunction "GPIO18_T47") (pintype "bidirectional"))
      (node (ref "CB1") (pin "T48") (pinfunction "GPIO18_T48") (pintype "bidirectional"))
      (node (ref "CB2") (pin "S47") (pinfunction "GPIO18_S47") (pintype "bidirectional"))
      (node (ref "CB2") (pin "S48") (pinfunction "GPIO18_S48") (pintype "bidirectional"))
      (node (ref "CB2") (pin "T47") (pinfunction "GPIO18_T47") (pintype "bidirectional"))
      (node (ref "CB2") (pin "T48") (pinfunction "GPIO18_T48") (pintype "bidirectional"))
      (node (ref "CB3") (pin "S47") (pinfunction "GPIO18_S47") (pintype "bidirectional"))
      (node (ref "CB3") (pin "S48") (pinfunction "GPIO18_S48") (pintype "bidirectional"))
      (node (ref "CB3") (pin "T47") (pinfunction "GPIO18_T47") (pintype "bidirectional"))
      (node (ref "CB3") (pin "T48") (pinfunction "GPIO18_T48") (pintype "bidirectional"))
      (node (ref "JP2") (pin "17") (pinfunction "17_17") (pintype "passive"))
      (node (ref "JP6") (pin "16") (pinfunction "16_16") (pintype "passive"))
      (node (ref "JP7") (pin "17") (pinfunction "17_17") (pintype "passive"))
      (node (ref "X1") (pin "4") (pinfunction "SCK_4") (pintype "input"))
    )
    (net (code "23") (name "/IO19") (class "Default")
      (node (ref "CB1") (pin "S49") (pinfunction "GPIO19_S49") (pintype "bidirectional"))
      (node (ref "CB1") (pin "S50") (pinfunction "GPIO19_S50") (pintype "bidirectional"))
      (node (ref "CB1") (pin "T49") (pinfunction "GPIO19_T49") (pintype "bidirectional"))
      (node (ref "CB1") (pin "T50") (pinfunction "GPIO19_T50") (pintype "bidirectional"))
      (node (ref "CB2") (pin "S49") (pinfunction "GPIO19_S49") (pintype "bidirectional"))
      (node (ref "CB2") (pin "S50") (pinfunction "GPIO19_S50") (pintype "bidirectional"))
      (node (ref "CB2") (pin "T49") (pinfunction "GPIO19_T49") (pintype "bidirectional"))
      (node (ref "CB2") (pin "T50") (pinfunction "GPIO19_T50") (pintype "bidirectional"))
      (node (ref "CB3") (pin "S49") (pinfunction "GPIO19_S49") (pintype "bidirectional"))
      (node (ref "CB3") (pin "S50") (pinfunction "GPIO19_S50") (pintype "bidirectional"))
      (node (ref "CB3") (pin "T49") (pinfunction "GPIO19_T49") (pintype "bidirectional"))
      (node (ref "CB3") (pin "T50") (pinfunction "GPIO19_T50") (pintype "bidirectional"))
      (node (ref "JP2") (pin "16") (pinfunction "16_16") (pintype "passive"))
      (node (ref "JP6") (pin "15") (pinfunction "15_15") (pintype "passive"))
      (node (ref "JP7") (pin "16") (pinfunction "16_16") (pintype "passive"))
      (node (ref "X1") (pin "5") (pinfunction "MOSI_5") (pintype "input"))
    )
    (net (code "24") (name "/IO20") (class "Default")
      (node (ref "CB1") (pin "S51") (pinfunction "GPIO20_S51") (pintype "bidirectional"))
      (node (ref "CB1") (pin "S52") (pinfunction "GPIO20_S52") (pintype "bidirectional"))
      (node (ref "CB1") (pin "T51") (pinfunction "GPIO20_T51") (pintype "bidirectional"))
      (node (ref "CB1") (pin "T52") (pinfunction "GPIO20_T52") (pintype "bidirectional"))
      (node (ref "CB2") (pin "S51") (pinfunction "GPIO20_S51") (pintype "bidirectional"))
      (node (ref "CB2") (pin "S52") (pinfunction "GPIO20_S52") (pintype "bidirectional"))
      (node (ref "CB2") (pin "T51") (pinfunction "GPIO20_T51") (pintype "bidirectional"))
      (node (ref "CB2") (pin "T52") (pinfunction "GPIO20_T52") (pintype "bidirectional"))
      (node (ref "CB3") (pin "S51") (pinfunction "GPIO20_S51") (pintype "bidirectional"))
      (node (ref "CB3") (pin "S52") (pinfunction "GPIO20_S52") (pintype "bidirectional"))
      (node (ref "CB3") (pin "T51") (pinfunction "GPIO20_T51") (pintype "bidirectional"))
      (node (ref "CB3") (pin "T52") (pinfunction "GPIO20_T52") (pintype "bidirectional"))
      (node (ref "JP2") (pin "15") (pinfunction "15_15") (pintype "passive"))
      (node (ref "JP6") (pin "14") (pinfunction "14_14") (pintype "passive"))
      (node (ref "JP7") (pin "15") (pinfunction "15_15") (pintype "passive"))
      (node (ref "X1") (pin "7") (pinfunction "DC_7") (pintype "input"))
    )
    (net (code "25") (name "/IO21") (class "Default")
      (node (ref "CB1") (pin "S53") (pinfunction "GPIO21_S53") (pintype "bidirectional"))
      (node (ref "CB1") (pin "S54") (pinfunction "GPIO21_S54") (pintype "bidirectional"))
      (node (ref "CB1") (pin "T53") (pinfunction "GPIO21_T53") (pintype "bidirectional"))
      (node (ref "CB1") (pin "T54") (pinfunction "GPIO21_T54") (pintype "bidirectional"))
      (node (ref "CB2") (pin "S53") (pinfunction "GPIO21_S53") (pintype "bidirectional"))
      (node (ref "CB2") (pin "S54") (pinfunction "GPIO21_S54") (pintype "bidirectional"))
      (node (ref "CB2") (pin "T53") (pinfunction "GPIO21_T53") (pintype "bidirectional"))
      (node (ref "CB2") (pin "T54") (pinfunction "GPIO21_T54") (pintype "bidirectional"))
      (node (ref "CB3") (pin "S53") (pinfunction "GPIO21_S53") (pintype "bidirectional"))
      (node (ref "CB3") (pin "S54") (pinfunction "GPIO21_S54") (pintype "bidirectional"))
      (node (ref "CB3") (pin "T53") (pinfunction "GPIO21_T53") (pintype "bidirectional"))
      (node (ref "CB3") (pin "T54") (pinfunction "GPIO21_T54") (pintype "bidirectional"))
      (node (ref "JP2") (pin "14") (pinfunction "14_14") (pintype "passive"))
      (node (ref "JP6") (pin "13") (pinfunction "13_13") (pintype "passive"))
      (node (ref "JP7") (pin "14") (pinfunction "14_14") (pintype "passive"))
      (node (ref "X1") (pin "9") (pinfunction "DISP_CS_9") (pintype "input"))
    )
    (net (code "26") (name "/IO22") (class "Default")
      (node (ref "CB1") (pin "S57") (pinfunction "GPIO22_S57") (pintype "bidirectional"))
      (node (ref "CB1") (pin "S58") (pinfunction "GPIO22_S58") (pintype "bidirectional"))
      (node (ref "CB1") (pin "T57") (pinfunction "GPIO22_T57") (pintype "bidirectional"))
      (node (ref "CB1") (pin "T58") (pinfunction "GPIO22_T58") (pintype "bidirectional"))
      (node (ref "CB2") (pin "S57") (pinfunction "GPIO22_S57") (pintype "bidirectional"))
      (node (ref "CB2") (pin "S58") (pinfunction "GPIO22_S58") (pintype "bidirectional"))
      (node (ref "CB2") (pin "T57") (pinfunction "GPIO22_T57") (pintype "bidirectional"))
      (node (ref "CB2") (pin "T58") (pinfunction "GPIO22_T58") (pintype "bidirectional"))
      (node (ref "CB3") (pin "S57") (pinfunction "GPIO22_S57") (pintype "bidirectional"))
      (node (ref "CB3") (pin "S58") (pinfunction "GPIO22_S58") (pintype "bidirectional"))
      (node (ref "CB3") (pin "T57") (pinfunction "GPIO22_T57") (pintype "bidirectional"))
      (node (ref "CB3") (pin "T58") (pinfunction "GPIO22_T58") (pintype "bidirectional"))
      (node (ref "JP2") (pin "12") (pinfunction "12_12") (pintype "passive"))
      (node (ref "JP6") (pin "11") (pinfunction "11_11") (pintype "passive"))
      (node (ref "JP7") (pin "12") (pinfunction "12_12") (pintype "passive"))
      (node (ref "X1") (pin "15") (pinfunction "INT_15") (pintype "output"))
    )
    (net (code "27") (name "/VREF") (class "Default")
      (node (ref "CB1") (pin "S69") (pinfunction "ADC_VREF_S69") (pintype "passive"))
      (node (ref "CB1") (pin "S70") (pinfunction "ADC_VREF_S70") (pintype "passive"))
      (node (ref "CB1") (pin "T69") (pinfunction "ADC_VREF_T69") (pintype "passive"))
      (node (ref "CB1") (pin "T70") (pinfunction "ADC_VREF_T70") (pintype "passive"))
      (node (ref "CB2") (pin "S69") (pinfunction "ADC_VREF_S69") (pintype "passive"))
      (node (ref "CB2") (pin "S70") (pinfunction "ADC_VREF_S70") (pintype "passive"))
      (node (ref "CB2") (pin "T69") (pinfunction "ADC_VREF_T69") (pintype "passive"))
      (node (ref "CB2") (pin "T70") (pinfunction "ADC_VREF_T70") (pintype "passive"))
      (node (ref "CB3") (pin "S69") (pinfunction "ADC_VREF_S69") (pintype "passive"))
      (node (ref "CB3") (pin "S70") (pinfunction "ADC_VREF_S70") (pintype "passive"))
      (node (ref "CB3") (pin "T69") (pinfunction "ADC_VREF_T69") (pintype "passive"))
      (node (ref "CB3") (pin "T70") (pinfunction "ADC_VREF_T70") (pintype "passive"))
      (node (ref "JP2") (pin "6") (pinfunction "6_6") (pintype "passive"))
      (node (ref "JP6") (pin "5") (pinfunction "5_5") (pintype "passive"))
      (node (ref "JP7") (pin "6") (pinfunction "6_6") (pintype "passive"))
    )
    (net (code "28") (name "/VSYS") (class "Default")
      (node (ref "CB1") (pin "S77") (pinfunction "VSYS_S77") (pintype "power_in"))
      (node (ref "CB1") (pin "S78") (pinfunction "VSYS_S78") (pintype "power_in"))
      (node (ref "CB1") (pin "T77") (pinfunction "VSYS_T77") (pintype "power_in"))
      (node (ref "CB1") (pin "T78") (pinfunction "VSYS_T78") (pintype "power_in"))
      (node (ref "CB2") (pin "S77") (pinfunction "VSYS_S77") (pintype "power_in"))
      (node (ref "CB2") (pin "S78") (pinfunction "VSYS_S78") (pintype "power_in"))
      (node (ref "CB2") (pin "T77") (pinfunction "VSYS_T77") (pintype "power_in"))
      (node (ref "CB2") (pin "T78") (pinfunction "VSYS_T78") (pintype "power_in"))
      (node (ref "CB3") (pin "S77") (pinfunction "VSYS_S77") (pintype "power_in"))
      (node (ref "CB3") (pin "S78") (pinfunction "VSYS_S78") (pintype "power_in"))
      (node (ref "CB3") (pin "T77") (pinfunction "VSYS_T77") (pintype "power_in"))
      (node (ref "CB3") (pin "T78") (pinfunction "VSYS_T78") (pintype "power_in"))
      (node (ref "JP2") (pin "2") (pinfunction "2_2") (pintype "passive"))
      (node (ref "JP6") (pin "1") (pinfunction "1_1") (pintype "passive"))
      (node (ref "JP7") (pin "2") (pinfunction "2_2") (pintype "passive"))
      (node (ref "Q3") (pin "2") (pinfunction "S_2") (pintype "passive"))
    )
    (net (code "29") (name "/~{EN}") (class "Default")
      (node (ref "CB1") (pin "S73") (pinfunction "3.3V_EN_S73") (pintype "passive"))
      (node (ref "CB1") (pin "S74") (pinfunction "3.3V_EN_S74") (pintype "passive"))
      (node (ref "CB1") (pin "T73") (pinfunction "3.3V_EN_T73") (pintype "passive"))
      (node (ref "CB1") (pin "T74") (pinfunction "3.3V_EN_T74") (pintype "passive"))
      (node (ref "CB2") (pin "S73") (pinfunction "3.3V_EN_S73") (pintype "passive"))
      (node (ref "CB2") (pin "S74") (pinfunction "3.3V_EN_S74") (pintype "passive"))
      (node (ref "CB2") (pin "T73") (pinfunction "3.3V_EN_T73") (pintype "passive"))
      (node (ref "CB2") (pin "T74") (pinfunction "3.3V_EN_T74") (pintype "passive"))
      (node (ref "CB3") (pin "S73") (pinfunction "3.3V_EN_S73") (pintype "passive"))
      (node (ref "CB3") (pin "S74") (pinfunction "3.3V_EN_S74") (pintype "passive"))
      (node (ref "CB3") (pin "T73") (pinfunction "3.3V_EN_T73") (pintype "passive"))
      (node (ref "CB3") (pin "T74") (pinfunction "3.3V_EN_T74") (pintype "passive"))
      (node (ref "ENA_SW") (pin "B") (pinfunction "P_B") (pintype "passive"))
      (node (ref "JP2") (pin "4") (pinfunction "4_4") (pintype "passive"))
      (node (ref "JP6") (pin "3") (pinfunction "3_3") (pintype "passive"))
      (node (ref "JP7") (pin "4") (pinfunction "4_4") (pintype "passive"))
    )
    (net (code "30") (name "/~{RESET}") (class "Default")
      (node (ref "CB1") (pin "S59") (pinfunction "/RUN_S59") (pintype "bidirectional"))
      (node (ref "CB1") (pin "S60") (pinfunction "/RUN_S60") (pintype "bidirectional"))
      (node (ref "CB1") (pin "T59") (pinfunction "/RUN_T59") (pintype "bidirectional"))
      (node (ref "CB1") (pin "T60") (pinfunction "/RUN_T60") (pintype "bidirectional"))
      (node (ref "CB2") (pin "S59") (pinfunction "/RUN_S59") (pintype "bidirectional"))
      (node (ref "CB2") (pin "S60") (pinfunction "/RUN_S60") (pintype "bidirectional"))
      (node (ref "CB2") (pin "T59") (pinfunction "/RUN_T59") (pintype "bidirectional"))
      (node (ref "CB2") (pin "T60") (pinfunction "/RUN_T60") (pintype "bidirectional"))
      (node (ref "CB3") (pin "S59") (pinfunction "/RUN_S59") (pintype "bidirectional"))
      (node (ref "CB3") (pin "S60") (pinfunction "/RUN_S60") (pintype "bidirectional"))
      (node (ref "CB3") (pin "T59") (pinfunction "/RUN_T59") (pintype "bidirectional"))
      (node (ref "CB3") (pin "T60") (pinfunction "/RUN_T60") (pintype "bidirectional"))
      (node (ref "JP2") (pin "11") (pinfunction "11_11") (pintype "passive"))
      (node (ref "JP6") (pin "10") (pinfunction "10_10") (pintype "passive"))
      (node (ref "JP7") (pin "11") (pinfunction "11_11") (pintype "passive"))
      (node (ref "SW1") (pin "1") (pinfunction "P_1") (pintype "passive"))
    )
    (net (code "31") (name "3.3V") (class "Default")
      (node (ref "CB1") (pin "S71") (pinfunction "3.3V_S71") (pintype "power_in"))
      (node (ref "CB1") (pin "S72") (pinfunction "3.3V_S72") (pintype "power_in"))
      (node (ref "CB1") (pin "T71") (pinfunction "3.3V_T71") (pintype "power_in"))
      (node (ref "CB1") (pin "T72") (pinfunction "3.3V_T72") (pintype "power_in"))
      (node (ref "CB2") (pin "S71") (pinfunction "3.3V_S71") (pintype "power_in"))
      (node (ref "CB2") (pin "S72") (pinfunction "3.3V_S72") (pintype "power_in"))
      (node (ref "CB2") (pin "T71") (pinfunction "3.3V_T71") (pintype "power_in"))
      (node (ref "CB2") (pin "T72") (pinfunction "3.3V_T72") (pintype "power_in"))
      (node (ref "CB3") (pin "S71") (pinfunction "3.3V_S71") (pintype "power_in"))
      (node (ref "CB3") (pin "S72") (pinfunction "3.3V_S72") (pintype "power_in"))
      (node (ref "CB3") (pin "T71") (pinfunction "3.3V_T71") (pintype "power_in"))
      (node (ref "CB3") (pin "T72") (pinfunction "3.3V_T72") (pintype "power_in"))
      (node (ref "CONN1") (pin "2") (pinfunction "V+_2") (pintype "passive"))
      (node (ref "JP2") (pin "5") (pinfunction "5_5") (pintype "passive"))
      (node (ref "JP6") (pin "4") (pinfunction "4_4") (pintype "passive"))
      (node (ref "JP7") (pin "5") (pinfunction "5_5") (pintype "passive"))
      (node (ref "LED3") (pin "2") (pinfunction "VDD_2") (pintype "power_in"))
      (node (ref "X1") (pin "1") (pinfunction "VCC_1") (pintype "power_in"))
    )
    (net (code "32") (name "GND") (class "Default")
      (node (ref "C1") (pin "2") (pinfunction "2_2") (pintype "passive"))
      (node (ref "C2") (pin "2") (pinfunction "2_2") (pintype "passive"))
      (node (ref "CB1") (pin "S15") (pinfunction "GND_S15") (pintype "power_in"))
      (node (ref "CB1") (pin "S16") (pinfunction "GND_S16") (pintype "power_in"))
      (node (ref "CB1") (pin "S25") (pinfunction "GND_S25") (pintype "power_in"))
      (node (ref "CB1") (pin "S26") (pinfunction "GND_S26") (pintype "power_in"))
      (node (ref "CB1") (pin "S35") (pinfunction "GND_S35") (pintype "power_in"))
      (node (ref "CB1") (pin "S36") (pinfunction "GND_S36") (pintype "power_in"))
      (node (ref "CB1") (pin "S45") (pinfunction "GND_S45") (pintype "power_in"))
      (node (ref "CB1") (pin "S46") (pinfunction "GND_S46") (pintype "power_in"))
      (node (ref "CB1") (pin "S5") (pinfunction "GND_S5") (pintype "power_in"))
      (node (ref "CB1") (pin "S55") (pinfunction "GND_S55") (pintype "power_in"))
      (node (ref "CB1") (pin "S56") (pinfunction "GND_S56") (pintype "power_in"))
      (node (ref "CB1") (pin "S6") (pinfunction "GND_S6") (pintype "power_in"))
      (node (ref "CB1") (pin "S65") (pinfunction "GND_S65") (pintype "power_in"))
      (node (ref "CB1") (pin "S66") (pinfunction "GND_S66") (pintype "power_in"))
      (node (ref "CB1") (pin "S75") (pinfunction "GND_S75") (pintype "power_in"))
      (node (ref "CB1") (pin "S76") (pinfunction "GND_S76") (pintype "power_in"))
      (node (ref "CB1") (pin "T15") (pinfunction "GND_T15") (pintype "power_in"))
      (node (ref "CB1") (pin "T16") (pinfunction "GND_T16") (pintype "power_in"))
      (node (ref "CB1") (pin "T25") (pinfunction "GND_T25") (pintype "power_in"))
      (node (ref "CB1") (pin "T26") (pinfunction "GND_T26") (pintype "power_in"))
      (node (ref "CB1") (pin "T35") (pinfunction "GND_T35") (pintype "power_in"))
      (node (ref "CB1") (pin "T36") (pinfunction "GND_T36") (pintype "power_in"))
      (node (ref "CB1") (pin "T45") (pinfunction "GND_T45") (pintype "power_in"))
      (node (ref "CB1") (pin "T46") (pinfunction "GND_T46") (pintype "power_in"))
      (node (ref "CB1") (pin "T5") (pinfunction "GND_T5") (pintype "power_in"))
      (node (ref "CB1") (pin "T55") (pinfunction "GND_T55") (pintype "power_in"))
      (node (ref "CB1") (pin "T56") (pinfunction "GND_T56") (pintype "power_in"))
      (node (ref "CB1") (pin "T6") (pinfunction "GND_T6") (pintype "power_in"))
      (node (ref "CB1") (pin "T65") (pinfunction "GND_T65") (pintype "power_in"))
      (node (ref "CB1") (pin "T66") (pinfunction "GND_T66") (pintype "power_in"))
      (node (ref "CB1") (pin "T75") (pinfunction "GND_T75") (pintype "power_in"))
      (node (ref "CB1") (pin "T76") (pinfunction "GND_T76") (pintype "power_in"))
      (node (ref "CB2") (pin "S15") (pinfunction "GND_S15") (pintype "power_in"))
      (node (ref "CB2") (pin "S16") (pinfunction "GND_S16") (pintype "power_in"))
      (node (ref "CB2") (pin "S25") (pinfunction "GND_S25") (pintype "power_in"))
      (node (ref "CB2") (pin "S26") (pinfunction "GND_S26") (pintype "power_in"))
      (node (ref "CB2") (pin "S35") (pinfunction "GND_S35") (pintype "power_in"))
      (node (ref "CB2") (pin "S36") (pinfunction "GND_S36") (pintype "power_in"))
      (node (ref "CB2") (pin "S45") (pinfunction "GND_S45") (pintype "power_in"))
      (node (ref "CB2") (pin "S46") (pinfunction "GND_S46") (pintype "power_in"))
      (node (ref "CB2") (pin "S5") (pinfunction "GND_S5") (pintype "power_in"))
      (node (ref "CB2") (pin "S55") (pinfunction "GND_S55") (pintype "power_in"))
      (node (ref "CB2") (pin "S56") (pinfunction "GND_S56") (pintype "power_in"))
      (node (ref "CB2") (pin "S6") (pinfunction "GND_S6") (pintype "power_in"))
      (node (ref "CB2") (pin "S65") (pinfunction "GND_S65") (pintype "power_in"))
      (node (ref "CB2") (pin "S66") (pinfunction "GND_S66") (pintype "power_in"))
      (node (ref "CB2") (pin "S75") (pinfunction "GND_S75") (pintype "power_in"))
      (node (ref "CB2") (pin "S76") (pinfunction "GND_S76") (pintype "power_in"))
      (node (ref "CB2") (pin "T15") (pinfunction "GND_T15") (pintype "power_in"))
      (node (ref "CB2") (pin "T16") (pinfunction "GND_T16") (pintype "power_in"))
      (node (ref "CB2") (pin "T25") (pinfunction "GND_T25") (pintype "power_in"))
      (node (ref "CB2") (pin "T26") (pinfunction "GND_T26") (pintype "power_in"))
      (node (ref "CB2") (pin "T35") (pinfunction "GND_T35") (pintype "power_in"))
      (node (ref "CB2") (pin "T36") (pinfunction "GND_T36") (pintype "power_in"))
      (node (ref "CB2") (pin "T45") (pinfunction "GND_T45") (pintype "power_in"))
      (node (ref "CB2") (pin "T46") (pinfunction "GND_T46") (pintype "power_in"))
      (node (ref "CB2") (pin "T5") (pinfunction "GND_T5") (pintype "power_in"))
      (node (ref "CB2") (pin "T55") (pinfunction "GND_T55") (pintype "power_in"))
      (node (ref "CB2") (pin "T56") (pinfunction "GND_T56") (pintype "power_in"))
      (node (ref "CB2") (pin "T6") (pinfunction "GND_T6") (pintype "power_in"))
      (node (ref "CB2") (pin "T65") (pinfunction "GND_T65") (pintype "power_in"))
      (node (ref "CB2") (pin "T66") (pinfunction "GND_T66") (pintype "power_in"))
      (node (ref "CB2") (pin "T75") (pinfunction "GND_T75") (pintype "power_in"))
      (node (ref "CB2") (pin "T76") (pinfunction "GND_T76") (pintype "power_in"))
      (node (ref "CB3") (pin "S15") (pinfunction "GND_S15") (pintype "power_in"))
      (node (ref "CB3") (pin "S16") (pinfunction "GND_S16") (pintype "power_in"))
      (node (ref "CB3") (pin "S25") (pinfunction "GND_S25") (pintype "power_in"))
      (node (ref "CB3") (pin "S26") (pinfunction "GND_S26") (pintype "power_in"))
      (node (ref "CB3") (pin "S35") (pinfunction "GND_S35") (pintype "power_in"))
      (node (ref "CB3") (pin "S36") (pinfunction "GND_S36") (pintype "power_in"))
      (node (ref "CB3") (pin "S45") (pinfunction "GND_S45") (pintype "power_in"))
      (node (ref "CB3") (pin "S46") (pinfunction "GND_S46") (pintype "power_in"))
      (node (ref "CB3") (pin "S5") (pinfunction "GND_S5") (pintype "power_in"))
      (node (ref "CB3") (pin "S55") (pinfunction "GND_S55") (pintype "power_in"))
      (node (ref "CB3") (pin "S56") (pinfunction "GND_S56") (pintype "power_in"))
      (node (ref "CB3") (pin "S6") (pinfunction "GND_S6") (pintype "power_in"))
      (node (ref "CB3") (pin "S65") (pinfunction "GND_S65") (pintype "power_in"))
      (node (ref "CB3") (pin "S66") (pinfunction "GND_S66") (pintype "power_in"))
      (node (ref "CB3") (pin "S75") (pinfunction "GND_S75") (pintype "power_in"))
      (node (ref "CB3") (pin "S76") (pinfunction "GND_S76") (pintype "power_in"))
      (node (ref "CB3") (pin "T15") (pinfunction "GND_T15") (pintype "power_in"))
      (node (ref "CB3") (pin "T16") (pinfunction "GND_T16") (pintype "power_in"))
      (node (ref "CB3") (pin "T25") (pinfunction "GND_T25") (pintype "power_in"))
      (node (ref "CB3") (pin "T26") (pinfunction "GND_T26") (pintype "power_in"))
      (node (ref "CB3") (pin "T35") (pinfunction "GND_T35") (pintype "power_in"))
      (node (ref "CB3") (pin "T36") (pinfunction "GND_T36") (pintype "power_in"))
      (node (ref "CB3") (pin "T45") (pinfunction "GND_T45") (pintype "power_in"))
      (node (ref "CB3") (pin "T46") (pinfunction "GND_T46") (pintype "power_in"))
      (node (ref "CB3") (pin "T5") (pinfunction "GND_T5") (pintype "power_in"))
      (node (ref "CB3") (pin "T55") (pinfunction "GND_T55") (pintype "power_in"))
      (node (ref "CB3") (pin "T56") (pinfunction "GND_T56") (pintype "power_in"))
      (node (ref "CB3") (pin "T6") (pinfunction "GND_T6") (pintype "power_in"))
      (node (ref "CB3") (pin "T65") (pinfunction "GND_T65") (pintype "power_in"))
      (node (ref "CB3") (pin "T66") (pinfunction "GND_T66") (pintype "power_in"))
      (node (ref "CB3") (pin "T75") (pinfunction "GND_T75") (pintype "power_in"))
      (node (ref "CB3") (pin "T76") (pinfunction "GND_T76") (pintype "power_in"))
      (node (ref "CONN1") (pin "1") (pinfunction "GND_1") (pintype "passive"))
      (node (ref "ENA_SW") (pin "A") (pinfunction "O_A") (pintype "passive"))
      (node (ref "JP1") (pin "13") (pinfunction "13_13") (pintype "passive"))
      (node (ref "JP1") (pin "18") (pinfunction "18_18") (pintype "passive"))
      (node (ref "JP1") (pin "3") (pinfunction "3_3") (pintype "passive"))
      (node (ref "JP1") (pin "8") (pinfunction "8_8") (pintype "passive"))
      (node (ref "JP2") (pin "13") (pinfunction "13_13") (pintype "passive"))
      (node (ref "JP2") (pin "18") (pinfunction "18_18") (pintype "passive"))
      (node (ref "JP2") (pin "3") (pinfunction "3_3") (pintype "passive"))
      (node (ref "JP2") (pin "8") (pinfunction "8_8") (pintype "passive"))
      (node (ref "JP5") (pin "13") (pinfunction "13_13") (pintype "passive"))
      (node (ref "JP5") (pin "18") (pinfunction "18_18") (pintype "passive"))
      (node (ref "JP5") (pin "3") (pinfunction "3_3") (pintype "passive"))
      (node (ref "JP5") (pin "8") (pinfunction "8_8") (pintype "passive"))
      (node (ref "JP6") (pin "12") (pinfunction "12_12") (pintype "passive"))
      (node (ref "JP6") (pin "17") (pinfunction "17_17") (pintype "passive"))
      (node (ref "JP6") (pin "2") (pinfunction "2_2") (pintype "passive"))
      (node (ref "JP6") (pin "7") (pinfunction "7_7") (pintype "passive"))
      (node (ref "JP7") (pin "13") (pinfunction "13_13") (pintype "passive"))
      (node (ref "JP7") (pin "18") (pinfunction "18_18") (pintype "passive"))
      (node (ref "JP7") (pin "3") (pinfunction "3_3") (pintype "passive"))
      (node (ref "JP7") (pin "8") (pinfunction "8_8") (pintype "passive"))
      (node (ref "JP8") (pin "1") (pinfunction "1_1") (pintype "passive"))
      (node (ref "JP8") (pin "11") (pinfunction "11_11") (pintype "passive"))
      (node (ref "JP8") (pin "16") (pinfunction "16_16") (pintype "passive"))
      (node (ref "JP8") (pin "6") (pinfunction "6_6") (pintype "passive"))
      (node (ref "LED2") (pin "C") (pinfunction "C_C") (pintype "passive"))
      (node (ref "LED3") (pin "4") (pinfunction "GND_4") (pintype "power_in"))
      (node (ref "R3") (pin "2") (pinfunction "2_2") (pintype "passive"))
      (node (ref "R5") (pin "1") (pinfunction "1_1") (pintype "passive"))
      (node (ref "R6") (pin "1") (pinfunction "1_1") (pintype "passive"))
      (node (ref "SJ1") (pin "2") (pinfunction "2_2") (pintype "passive"))
      (node (ref "SW1") (pin "2") (pinfunction "S_2") (pintype "passive"))
      (node (ref "SW1") (pin "MT1") (pinfunction "MT_MT1") (pintype "bidirectional"))
      (node (ref "SW1") (pin "MT2") (pinfunction "MT_MT2") (pintype "bidirectional"))
      (node (ref "U1") (pin "2") (pinfunction "VSS_2") (pintype "power_in"))
      (node (ref "X1") (pin "3") (pinfunction "GND_3") (pintype "power_in"))
      (node (ref "X1") (pin "SUPPORT1") (pinfunction "GND_SUPPORT1") (pintype "power_in"))
      (node (ref "X1") (pin "SUPPORT2") (pinfunction "GND_SUPPORT2") (pintype "power_in"))
      (node (ref "X3") (pin "1") (pinfunction "1_1") (pintype "passive"))
      (node (ref "X3") (pin "NC1") (pinfunction "P$1_NC1") (pintype "bidirectional"))
      (node (ref "X3") (pin "NC2") (pinfunction "P$1_NC2") (pintype "bidirectional"))
    )
    (net (code "33") (name "Net-(LED1-PadC)") (class "Default")
      (node (ref "LED1") (pin "C") (pinfunction "C_C") (pintype "passive"))
      (node (ref "R1") (pin "1") (pinfunction "1_1") (pintype "passive"))
    )
    (net (code "34") (name "Net-(LED2-PadA)") (class "Default")
      (node (ref "LED2") (pin "A") (pinfunction "A_A") (pintype "passive"))
      (node (ref "R2") (pin "1") (pinfunction "1_1") (pintype "passive"))
    )
    (net (code "35") (name "Net-(LED3-DI)") (class "Default")
      (node (ref "LED3") (pin "1") (pinfunction "DI_1") (pintype "input"))
      (node (ref "R6") (pin "2") (pinfunction "2_2") (pintype "passive"))
      (node (ref "SJ3") (pin "2") (pinfunction "2_2") (pintype "passive"))
    )
    (net (code "36") (name "Net-(R4-Pad2)") (class "Default")
      (node (ref "R4") (pin "2") (pinfunction "2_2") (pintype "passive"))
      (node (ref "SJ1") (pin "1") (pinfunction "1_1") (pintype "passive"))
    )
    (net (code "37") (name "Net-(U1-PROG)") (class "Default")
      (node (ref "R3") (pin "1") (pinfunction "1_1") (pintype "passive"))
      (node (ref "R4") (pin "1") (pinfunction "1_1") (pintype "passive"))
      (node (ref "U1") (pin "5") (pinfunction "PROG_5") (pintype "input"))
    )
    (net (code "38") (name "Net-(U1-STAT)") (class "Default")
      (node (ref "R1") (pin "2") (pinfunction "2_2") (pintype "passive"))
      (node (ref "R2") (pin "2") (pinfunction "2_2") (pintype "passive"))
      (node (ref "U1") (pin "1") (pinfunction "STAT_1") (pintype "output"))
    )
    (net (code "39") (name "Net-(U1-VBAT)") (class "Default")
      (node (ref "SJ2") (pin "1") (pinfunction "1_1") (pintype "passive"))
      (node (ref "U1") (pin "3") (pinfunction "VBAT_3") (pintype "power_in"))
    )
    (net (code "40") (name "VBAT") (class "Default")
      (node (ref "C2") (pin "1") (pinfunction "1_1") (pintype "passive"))
      (node (ref "Q3") (pin "3") (pinfunction "D_3") (pintype "passive"))
      (node (ref "SJ2") (pin "2") (pinfunction "2_2") (pintype "passive"))
      (node (ref "X3") (pin "2") (pinfunction "2_2") (pintype "passive"))
    )
    (net (code "41") (name "VBUS") (class "Default")
      (node (ref "C1") (pin "1") (pinfunction "1_1") (pintype "passive"))
      (node (ref "CB1") (pin "S79") (pinfunction "VBUS_S79") (pintype "power_in"))
      (node (ref "CB1") (pin "S80") (pinfunction "VBUS_S80") (pintype "power_in"))
      (node (ref "CB1") (pin "T79") (pinfunction "VBUS_T79") (pintype "power_in"))
      (node (ref "CB1") (pin "T80") (pinfunction "VBUS_T80") (pintype "power_in"))
      (node (ref "CB2") (pin "S79") (pinfunction "VBUS_S79") (pintype "power_in"))
      (node (ref "CB2") (pin "S80") (pinfunction "VBUS_S80") (pintype "power_in"))
      (node (ref "CB2") (pin "T79") (pinfunction "VBUS_T79") (pintype "power_in"))
      (node (ref "CB2") (pin "T80") (pinfunction "VBUS_T80") (pintype "power_in"))
      (node (ref "CB3") (pin "S79") (pinfunction "VBUS_S79") (pintype "power_in"))
      (node (ref "CB3") (pin "S80") (pinfunction "VBUS_S80") (pintype "power_in"))
      (node (ref "CB3") (pin "T79") (pinfunction "VBUS_T79") (pintype "power_in"))
      (node (ref "CB3") (pin "T80") (pinfunction "VBUS_T80") (pintype "power_in"))
      (node (ref "JP2") (pin "1") (pinfunction "1_1") (pintype "passive"))
      (node (ref "JP7") (pin "1") (pinfunction "1_1") (pintype "passive"))
      (node (ref "LED1") (pin "A") (pinfunction "A_A") (pintype "passive"))
      (node (ref "Q3") (pin "1") (pinfunction "G_1") (pintype "passive"))
      (node (ref "R5") (pin "2") (pinfunction "2_2") (pintype "passive"))
      (node (ref "U1") (pin "4") (pinfunction "VDD_4") (pintype "power_in"))
    )
    (net (code "42") (name "unconnected-(ENA_SW-S-PadC)") (class "Default")
      (node (ref "ENA_SW") (pin "C") (pinfunction "S_C") (pintype "passive"))
    )
    (net (code "43") (name "unconnected-(LED3-DO-Pad3)") (class "Default")
      (node (ref "LED3") (pin "3") (pinfunction "DO_3") (pintype "output"))
    )
    (net (code "44") (name "unconnected-(X1-BUSY{slash}TE-Pad16)") (class "Default")
      (node (ref "X1") (pin "16") (pinfunction "BUSY/TE_16") (pintype "output"))
    )
    (net (code "45") (name "unconnected-(X1-GPIO1-Pad17)") (class "Default")
      (node (ref "X1") (pin "17") (pinfunction "GPIO1_17") (pintype "passive"))
    )
    (net (code "46") (name "unconnected-(X1-GPIO2-Pad18)") (class "Default")
      (node (ref "X1") (pin "18") (pinfunction "GPIO2_18") (pintype "passive"))
    )
    (net (code "47") (name "unconnected-(X1-MEM_CS-Pad11)") (class "Default")
      (node (ref "X1") (pin "11") (pinfunction "MEM_CS_11") (pintype "input"))
    )
    (net (code "48") (name "unconnected-(X1-RESET-Pad8)") (class "Default")
      (node (ref "X1") (pin "8") (pinfunction "RESET_8") (pintype "input"))
    )
  )
)
